# JTAG.net
KiCad netlist of a schematic drawn in Altium Designer
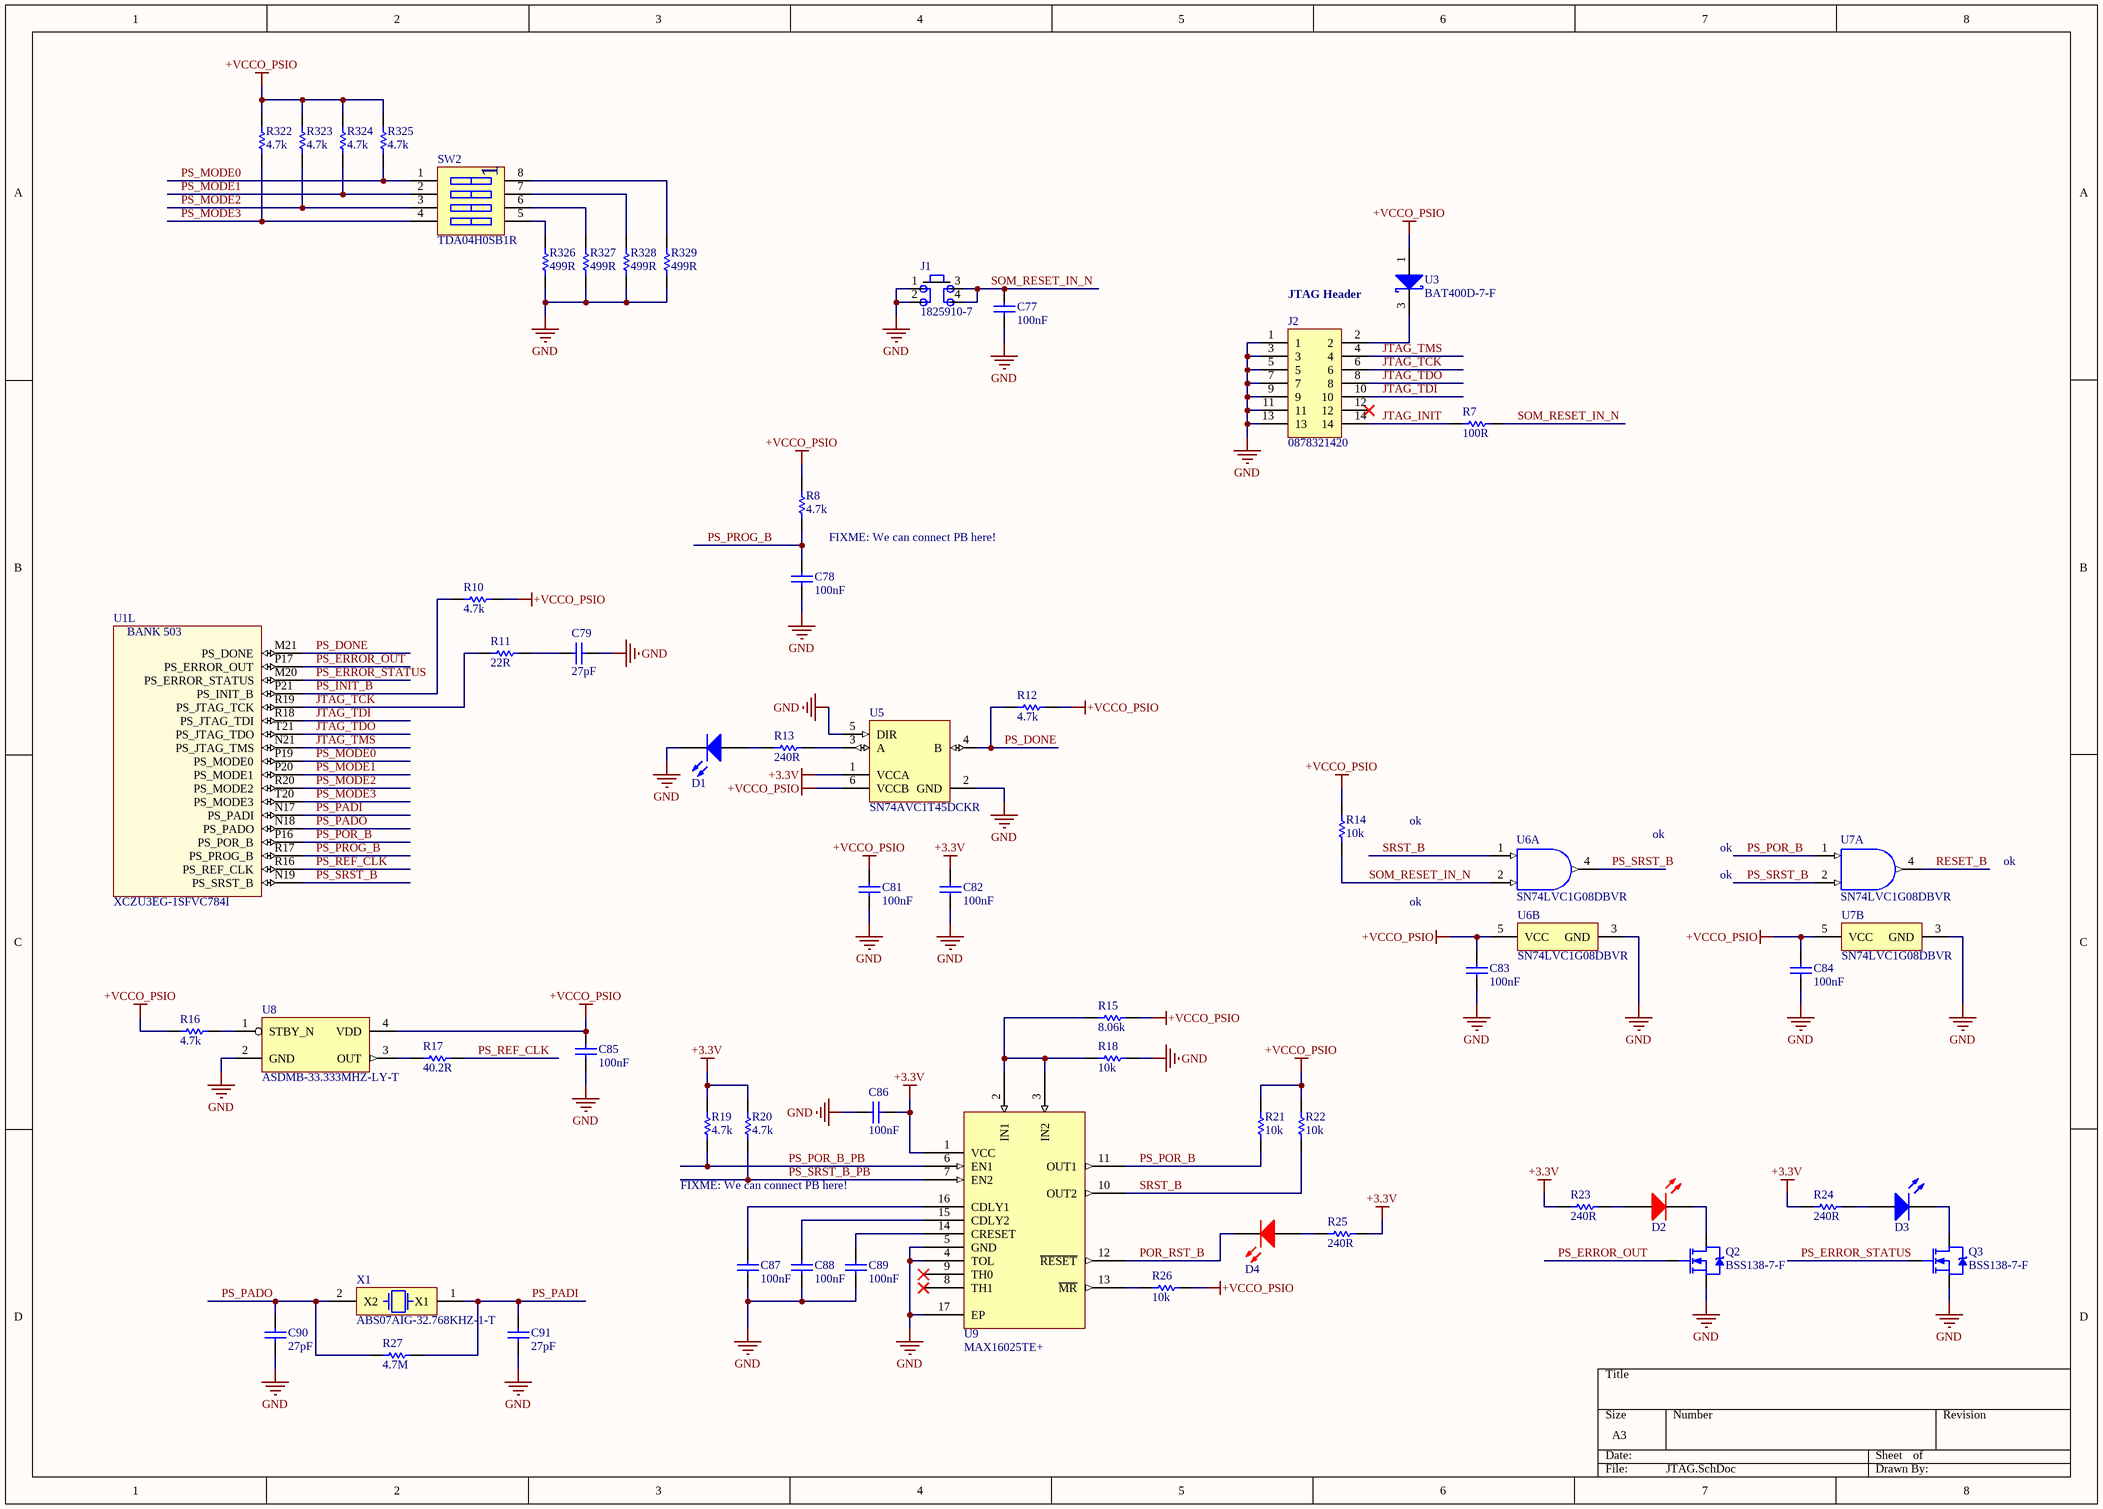
[diagram p0: JTAG.SchDoc]

(export (version "E")
  (design (tool "Eeschema 10.0.6"))
  (components
    (comp (ref "C77")
      (value "100nF")
      (footprint "CAPC1005L_0402")
      (description "CAP CER 0.1UF 25V X7R 0402")
      (fields (field (name "VOLTAGE") "25V") (field (name "TOLERANCE") "10%"))
      (libsource (lib "Ultrascale_SchLib") (part "CAPCER0402X7R100N25V_10T"))
    )
    (comp (ref "C78")
      (value "100nF")
      (footprint "CAPC1005L_0402")
      (description "CAP CER 0.1UF 25V X7R 0402")
      (fields (field (name "VOLTAGE") "25V") (field (name "TOLERANCE") "10%"))
      (libsource (lib "Ultrascale_SchLib") (part "CAPCER0402X7R100N25V_10T"))
    )
    (comp (ref "C79")
      (value "27pF")
      (footprint "CAPC1005L_0402")
      (description "CAP CER 27PF 50V C0G/NP0 0402")
      (fields (field (name "VOLTAGE") "50V") (field (name "TOLERANCE") "5%"))
      (libsource (lib "Ultrascale_SchLib") (part "CAPCER0402C0G27P50V_5T"))
    )
    (comp (ref "C81")
      (value "100nF")
      (footprint "CAPC1005L_0402")
      (description "CAP CER 0.1UF 25V X7R 0402")
      (fields (field (name "VOLTAGE") "25V") (field (name "TOLERANCE") "10%"))
      (libsource (lib "Ultrascale_SchLib") (part "CAPCER0402X7R100N25V_10T"))
    )
    (comp (ref "C82")
      (value "100nF")
      (footprint "CAPC1005L_0402")
      (description "CAP CER 0.1UF 25V X7R 0402")
      (fields (field (name "VOLTAGE") "25V") (field (name "TOLERANCE") "10%"))
      (libsource (lib "Ultrascale_SchLib") (part "CAPCER0402X7R100N25V_10T"))
    )
    (comp (ref "C83")
      (value "100nF")
      (footprint "CAPC1005L_0402")
      (description "CAP CER 0.1UF 25V X7R 0402")
      (fields (field (name "VOLTAGE") "25V") (field (name "TOLERANCE") "10%"))
      (libsource (lib "Ultrascale_SchLib") (part "CAPCER0402X7R100N25V_10T"))
    )
    (comp (ref "C84")
      (value "100nF")
      (footprint "CAPC1005L_0402")
      (description "CAP CER 0.1UF 25V X7R 0402")
      (fields (field (name "VOLTAGE") "25V") (field (name "TOLERANCE") "10%"))
      (libsource (lib "Ultrascale_SchLib") (part "CAPCER0402X7R100N25V_10T"))
    )
    (comp (ref "C85")
      (value "100nF")
      (footprint "CAPC1005L_0402")
      (description "CAP CER 0.1UF 25V X7R 0402")
      (fields (field (name "VOLTAGE") "25V") (field (name "TOLERANCE") "10%"))
      (libsource (lib "Ultrascale_SchLib") (part "CAPCER0402X7R100N25V_10T"))
    )
    (comp (ref "C86")
      (value "100nF")
      (footprint "CAPC1005L_0402")
      (description "CAP CER 0.1UF 25V X7R 0402")
      (fields (field (name "VOLTAGE") "25V") (field (name "TOLERANCE") "10%"))
      (libsource (lib "Ultrascale_SchLib") (part "CAPCER0402X7R100N25V_10T"))
    )
    (comp (ref "C87")
      (value "100nF")
      (footprint "CAPC1005L_0402")
      (description "CAP CER 0.1UF 25V X7R 0402")
      (fields (field (name "VOLTAGE") "25V") (field (name "TOLERANCE") "10%"))
      (libsource (lib "Ultrascale_SchLib") (part "CAPCER0402X7R100N25V_10T"))
    )
    (comp (ref "C88")
      (value "100nF")
      (footprint "CAPC1005L_0402")
      (description "CAP CER 0.1UF 25V X7R 0402")
      (fields (field (name "VOLTAGE") "25V") (field (name "TOLERANCE") "10%"))
      (libsource (lib "Ultrascale_SchLib") (part "CAPCER0402X7R100N25V_10T"))
    )
    (comp (ref "C89")
      (value "100nF")
      (footprint "CAPC1005L_0402")
      (description "CAP CER 0.1UF 25V X7R 0402")
      (fields (field (name "VOLTAGE") "25V") (field (name "TOLERANCE") "10%"))
      (libsource (lib "Ultrascale_SchLib") (part "CAPCER0402X7R100N25V_10T"))
    )
    (comp (ref "C90")
      (value "27pF")
      (footprint "CAPC1005L_0402")
      (description "CAP CER 27PF 50V C0G/NP0 0402")
      (fields (field (name "VOLTAGE") "50V") (field (name "TOLERANCE") "5%"))
      (libsource (lib "Ultrascale_SchLib") (part "CAPCER0402C0G27P50V_5T"))
    )
    (comp (ref "C91")
      (value "27pF")
      (footprint "CAPC1005L_0402")
      (description "CAP CER 27PF 50V C0G/NP0 0402")
      (fields (field (name "VOLTAGE") "50V") (field (name "TOLERANCE") "5%"))
      (libsource (lib "Ultrascale_SchLib") (part "CAPCER0402C0G27P50V_5T"))
    )
    (comp (ref "D1")
      (value "LED0603BLUE")
      (footprint "LED0603BLUE")
      (description "LED BLUE DIFFUSED 0603 SMD")
      (libsource (lib "Ultrascale_SchLib") (part "LED0603BLUE"))
    )
    (comp (ref "D2")
      (value "LED0603RED")
      (footprint "LED0603RED")
      (description "LED RED DIFFUSED 0603 SMD")
      (libsource (lib "Ultrascale_SchLib") (part "LED0603RED"))
    )
    (comp (ref "D3")
      (value "LED0603GREEN")
      (footprint "LED0603GREEN")
      (description "LED GREEN DIFFUSED 0603 SMD")
      (libsource (lib "Ultrascale_SchLib") (part "LED0603GREEN"))
    )
    (comp (ref "D4")
      (value "LED0603RED")
      (footprint "LED0603RED")
      (description "LED RED DIFFUSED 0603 SMD")
      (libsource (lib "Ultrascale_SchLib") (part "LED0603RED"))
    )
    (comp (ref "J1")
      (value "1825910-7")
      (footprint "PB_1825910-7")
      (description "SWITCH TACTILE SPST-NO 0.05A 24V")
      (libsource (lib "Ultrascale_SchLib") (part "1825910-7"))
    )
    (comp (ref "J2")
      (value "0878321420")
      (footprint "0878321420")
      (description "CONN HEADER 14POS 2MM VERT SMD")
      (libsource (lib "Ultrascale_SchLib") (part "0878321420"))
    )
    (comp (ref "Q2")
      (value "BSS138-7-F")
      (footprint "DIODES_SOT23")
      (description "MOSFET N-CH 50V 200MA SOT23-3")
      (libsource (lib "Ultrascale_SchLib") (part "BSS138-7-F"))
    )
    (comp (ref "Q3")
      (value "BSS138-7-F")
      (footprint "DIODES_SOT23")
      (description "MOSFET N-CH 50V 200MA SOT23-3")
      (libsource (lib "Ultrascale_SchLib") (part "BSS138-7-F"))
    )
    (comp (ref "R7")
      (value "100R")
      (footprint "RESC1005L_0402")
      (description "RES SMD 100 OHM 1% 1/10W 0402")
      (fields (field (name "POWER") "1/10W") (field (name "TOLERANCE") "1%"))
      (libsource (lib "Ultrascale_SchLib") (part "RES0402_100R_0W1_1T"))
    )
    (comp (ref "R8")
      (value "4.7k")
      (footprint "RESC1005L_0402")
      (description "RES SMD 4.7K OHM 1% 1/10W 0402")
      (fields (field (name "POWER") "1/10W") (field (name "TOLERANCE") "1%"))
      (libsource (lib "Ultrascale_SchLib") (part "RES0402_4K7_0W1_1T"))
    )
    (comp (ref "R10")
      (value "4.7k")
      (footprint "RESC1005L_0402")
      (description "RES SMD 4.7K OHM 1% 1/10W 0402")
      (fields (field (name "POWER") "1/10W") (field (name "TOLERANCE") "1%"))
      (libsource (lib "Ultrascale_SchLib") (part "RES0402_4K7_0W1_1T"))
    )
    (comp (ref "R11")
      (value "22R")
      (footprint "RESC1005L_0402")
      (description "RES SMD 22 OHM 1% 1/10W 0402")
      (fields (field (name "POWER") "1/10W") (field (name "TOLERANCE") "1%"))
      (libsource (lib "Ultrascale_SchLib") (part "RES0402_22R_0W1_1T"))
    )
    (comp (ref "R12")
      (value "4.7k")
      (footprint "RESC1005L_0402")
      (description "RES SMD 4.7K OHM 1% 1/10W 0402")
      (fields (field (name "POWER") "1/10W") (field (name "TOLERANCE") "1%"))
      (libsource (lib "Ultrascale_SchLib") (part "RES0402_4K7_0W1_1T"))
    )
    (comp (ref "R13")
      (value "240R")
      (footprint "RESC1005L_0402")
      (description "RES SMD 240 OHM 1% 1/10W 0402")
      (fields (field (name "POWER") "1/10W") (field (name "TOLERANCE") "1%"))
      (libsource (lib "Ultrascale_SchLib") (part "RES0402_240R_0W1_1T"))
    )
    (comp (ref "R14")
      (value "10k")
      (footprint "RESC1005L_0402")
      (description "RES SMD 10K OHM 0.5% 1/16W 0402")
      (fields (field (name "POWER") "1/16W") (field (name "TOLERANCE") "0.5%"))
      (libsource (lib "Ultrascale_SchLib") (part "RES0402_10K_0W1_05T"))
    )
    (comp (ref "R15")
      (value "8.06k")
      (footprint "RESC1005L_0402")
      (description "RES SMD 8.06K OHM 1% 1/10W 0402")
      (fields (field (name "POWER") "1/10W") (field (name "TOLERANCE") "1%"))
      (libsource (lib "Ultrascale_SchLib") (part "RES0402_8K06_0W1_1T"))
    )
    (comp (ref "R16")
      (value "4.7k")
      (footprint "RESC1005L_0402")
      (description "RES SMD 4.7K OHM 1% 1/10W 0402")
      (fields (field (name "POWER") "1/10W") (field (name "TOLERANCE") "1%"))
      (libsource (lib "Ultrascale_SchLib") (part "RES0402_4K7_0W1_1T"))
    )
    (comp (ref "R17")
      (value "40.2R")
      (footprint "RESC1005L_0402")
      (description "RES SMD 40.2 OHM 1% 1/10W 0402")
      (fields (field (name "POWER") "1/10W") (field (name "TOLERANCE") "1%"))
      (libsource (lib "Ultrascale_SchLib") (part "RES0402_40R2_0W1_1T"))
    )
    (comp (ref "R18")
      (value "10k")
      (footprint "RESC1005L_0402")
      (description "RES SMD 10K OHM 0.5% 1/16W 0402")
      (fields (field (name "POWER") "1/16W") (field (name "TOLERANCE") "0.5%"))
      (libsource (lib "Ultrascale_SchLib") (part "RES0402_10K_0W1_05T"))
    )
    (comp (ref "R19")
      (value "4.7k")
      (footprint "RESC1005L_0402")
      (description "RES SMD 4.7K OHM 1% 1/10W 0402")
      (fields (field (name "POWER") "1/10W") (field (name "TOLERANCE") "1%"))
      (libsource (lib "Ultrascale_SchLib") (part "RES0402_4K7_0W1_1T"))
    )
    (comp (ref "R20")
      (value "4.7k")
      (footprint "RESC1005L_0402")
      (description "RES SMD 4.7K OHM 1% 1/10W 0402")
      (fields (field (name "POWER") "1/10W") (field (name "TOLERANCE") "1%"))
      (libsource (lib "Ultrascale_SchLib") (part "RES0402_4K7_0W1_1T"))
    )
    (comp (ref "R21")
      (value "10k")
      (footprint "RESC1005L_0402")
      (description "RES SMD 10K OHM 0.5% 1/16W 0402")
      (fields (field (name "POWER") "1/16W") (field (name "TOLERANCE") "0.5%"))
      (libsource (lib "Ultrascale_SchLib") (part "RES0402_10K_0W1_05T"))
    )
    (comp (ref "R22")
      (value "10k")
      (footprint "RESC1005L_0402")
      (description "RES SMD 10K OHM 0.5% 1/16W 0402")
      (fields (field (name "POWER") "1/16W") (field (name "TOLERANCE") "0.5%"))
      (libsource (lib "Ultrascale_SchLib") (part "RES0402_10K_0W1_05T"))
    )
    (comp (ref "R23")
      (value "240R")
      (footprint "RESC1005L_0402")
      (description "RES SMD 240 OHM 1% 1/10W 0402")
      (fields (field (name "POWER") "1/10W") (field (name "TOLERANCE") "1%"))
      (libsource (lib "Ultrascale_SchLib") (part "RES0402_240R_0W1_1T"))
    )
    (comp (ref "R24")
      (value "240R")
      (footprint "RESC1005L_0402")
      (description "RES SMD 240 OHM 1% 1/10W 0402")
      (fields (field (name "POWER") "1/10W") (field (name "TOLERANCE") "1%"))
      (libsource (lib "Ultrascale_SchLib") (part "RES0402_240R_0W1_1T"))
    )
    (comp (ref "R25")
      (value "240R")
      (footprint "RESC1005L_0402")
      (description "RES SMD 240 OHM 1% 1/10W 0402")
      (fields (field (name "POWER") "1/10W") (field (name "TOLERANCE") "1%"))
      (libsource (lib "Ultrascale_SchLib") (part "RES0402_240R_0W1_1T"))
    )
    (comp (ref "R26")
      (value "10k")
      (footprint "RESC1005L_0402")
      (description "RES SMD 10K OHM 0.5% 1/16W 0402")
      (fields (field (name "POWER") "1/16W") (field (name "TOLERANCE") "0.5%"))
      (libsource (lib "Ultrascale_SchLib") (part "RES0402_10K_0W1_05T"))
    )
    (comp (ref "R27")
      (value "4.7M")
      (footprint "RESC1005L_0402")
      (description "RES SMD 4.7M OHM 5% 1/16W 0402")
      (fields (field (name "POWER") "1/10W") (field (name "TOLERANCE") "5%"))
      (libsource (lib "Ultrascale_SchLib") (part "RES0402_4M7_0W1_5T"))
    )
    (comp (ref "R322")
      (value "4.7k")
      (footprint "RESC1005L_0402")
      (description "RES SMD 4.7K OHM 1% 1/10W 0402")
      (fields (field (name "POWER") "1/10W") (field (name "TOLERANCE") "1%"))
      (libsource (lib "Ultrascale_SchLib") (part "RES0402_4K7_0W1_1T"))
    )
    (comp (ref "R323")
      (value "4.7k")
      (footprint "RESC1005L_0402")
      (description "RES SMD 4.7K OHM 1% 1/10W 0402")
      (fields (field (name "POWER") "1/10W") (field (name "TOLERANCE") "1%"))
      (libsource (lib "Ultrascale_SchLib") (part "RES0402_4K7_0W1_1T"))
    )
    (comp (ref "R324")
      (value "4.7k")
      (footprint "RESC1005L_0402")
      (description "RES SMD 4.7K OHM 1% 1/10W 0402")
      (fields (field (name "POWER") "1/10W") (field (name "TOLERANCE") "1%"))
      (libsource (lib "Ultrascale_SchLib") (part "RES0402_4K7_0W1_1T"))
    )
    (comp (ref "R325")
      (value "4.7k")
      (footprint "RESC1005L_0402")
      (description "RES SMD 4.7K OHM 1% 1/10W 0402")
      (fields (field (name "POWER") "1/10W") (field (name "TOLERANCE") "1%"))
      (libsource (lib "Ultrascale_SchLib") (part "RES0402_4K7_0W1_1T"))
    )
    (comp (ref "R326")
      (value "499R")
      (footprint "RESC1005L_0402")
      (description "RES SMD 499 OHM 1% 1/16W 0402")
      (fields (field (name "POWER") "1/10W") (field (name "TOLERANCE") "1%"))
      (libsource (lib "Ultrascale_SchLib") (part "RES0402_499R_0W1_1T"))
    )
    (comp (ref "R327")
      (value "499R")
      (footprint "RESC1005L_0402")
      (description "RES SMD 499 OHM 1% 1/16W 0402")
      (fields (field (name "POWER") "1/10W") (field (name "TOLERANCE") "1%"))
      (libsource (lib "Ultrascale_SchLib") (part "RES0402_499R_0W1_1T"))
    )
    (comp (ref "R328")
      (value "499R")
      (footprint "RESC1005L_0402")
      (description "RES SMD 499 OHM 1% 1/16W 0402")
      (fields (field (name "POWER") "1/10W") (field (name "TOLERANCE") "1%"))
      (libsource (lib "Ultrascale_SchLib") (part "RES0402_499R_0W1_1T"))
    )
    (comp (ref "R329")
      (value "499R")
      (footprint "RESC1005L_0402")
      (description "RES SMD 499 OHM 1% 1/16W 0402")
      (fields (field (name "POWER") "1/10W") (field (name "TOLERANCE") "1%"))
      (libsource (lib "Ultrascale_SchLib") (part "RES0402_499R_0W1_1T"))
    )
    (comp (ref "SW2")
      (value "TDA04H0SB1R")
      (footprint "4POS_DIP_SWITCH")
      (description "SWITCH SLIDE DIP SPST 25MA 24V")
      (libsource (lib "Ultrascale_SchLib") (part "TDA04H0SB1R"))
    )
    (comp (ref "U1")
      (value "XCZU3EG-1SFVC784I")
      (footprint "BGA784x28")
      (description "IC FPGA 252 I/O 784FCBGA - XILINX ZYNQ ULTRASCALE+")
      (libsource (lib "Ultrascale_SchLib") (part "XCZU3EG-1SFVC784I"))
    )
    (comp (ref "U3")
      (value "BAT400D-7-F")
      (footprint "BAT400D-7-F _SOT23")
      (description "DIODE SCHOTTKY 40V 500MA SOT23-3")
      (libsource (lib "Ultrascale_SchLib") (part "BAT400D-7-F"))
    )
    (comp (ref "U5")
      (value "SN74AVC1T45DCKR")
      (footprint "DCK0006A_N")
      (fields (field (name "GENERIC PART NUMBER") "SN74AVC1T45"))
      (libsource (lib "Ultrascale_SchLib") (part "SN74AVC1T45DCKR"))
    )
    (comp (ref "U6")
      (value "SN74LVC1G08DBVR")
      (footprint "DBV0005A_N")
      (description "Single 2-Input Positive-AND Gate, DBV0005A, LARGE T&R")
      (fields (field (name "GENERIC PART NUMBER") "SN74LVC1G08"))
      (libsource (lib "Ultrascale_SchLib") (part "SN74LVC1G08DBVR"))
    )
    (comp (ref "U7")
      (value "SN74LVC1G08DBVR")
      (footprint "DBV0005A_N")
      (description "Single 2-Input Positive-AND Gate, DBV0005A, LARGE T&R")
      (fields (field (name "GENERIC PART NUMBER") "SN74LVC1G08"))
      (libsource (lib "Ultrascale_SchLib") (part "SN74LVC1G08DBVR"))
    )
    (comp (ref "U8")
      (value "ASDMB-33.333MHZ-LY-T")
      (footprint "ASDMB")
      (description "OSC MEMS 33.333MHZ CMOS SMD")
      (libsource (lib "Ultrascale_SchLib") (part "ASDMB-33.333MHZ-LY-T"))
    )
    (comp (ref "U9")
      (value "MAX16025TE+")
      (footprint "T1644+4_L")
      (description "IC SUPERVISORY CIRC DL 16TQFN")
      (libsource (lib "Ultrascale_SchLib") (part "MAX16025TE+"))
    )
    (comp (ref "X1")
      (value "ABS07AIG-32.768KHZ-1-T")
      (footprint "ABS07")
      (description "CRYSTAL 32.768KHZ 12.5PF SMD")
      (libsource (lib "Ultrascale_SchLib") (part "ABS07AIG-32.768KHZ-1-T"))
    )
  )
  (nets
    (net (code "1") (name "+3.3V") (class "Default")
      (node (ref "C82") (pin "1") (pinfunction "1_1") (pintype "passive"))
      (node (ref "C86") (pin "1") (pinfunction "1_1") (pintype "passive"))
      (node (ref "R19") (pin "1") (pinfunction "1_1") (pintype "passive"))
      (node (ref "R20") (pin "1") (pinfunction "1_1") (pintype "passive"))
      (node (ref "R23") (pin "1") (pinfunction "1_1") (pintype "passive"))
      (node (ref "R24") (pin "1") (pinfunction "1_1") (pintype "passive"))
      (node (ref "R25") (pin "2") (pinfunction "2_2") (pintype "passive"))
      (node (ref "U5") (pin "1") (pinfunction "VCCA_1") (pintype "power_in"))
      (node (ref "U9") (pin "1") (pinfunction "VCC_1") (pintype "passive"))
    )
    (net (code "2") (name "+VCCO_PSIO") (class "Default")
      (node (ref "C81") (pin "1") (pinfunction "1_1") (pintype "passive"))
      (node (ref "C83") (pin "1") (pinfunction "1_1") (pintype "passive"))
      (node (ref "C84") (pin "1") (pinfunction "1_1") (pintype "passive"))
      (node (ref "C85") (pin "1") (pinfunction "1_1") (pintype "passive"))
      (node (ref "R10") (pin "2") (pinfunction "2_2") (pintype "passive"))
      (node (ref "R12") (pin "2") (pinfunction "2_2") (pintype "passive"))
      (node (ref "R14") (pin "1") (pinfunction "1_1") (pintype "passive"))
      (node (ref "R15") (pin "2") (pinfunction "2_2") (pintype "passive"))
      (node (ref "R16") (pin "1") (pinfunction "1_1") (pintype "passive"))
      (node (ref "R21") (pin "1") (pinfunction "1_1") (pintype "passive"))
      (node (ref "R22") (pin "1") (pinfunction "1_1") (pintype "passive"))
      (node (ref "R26") (pin "1") (pinfunction "1_1") (pintype "passive"))
      (node (ref "R322") (pin "2") (pinfunction "2_2") (pintype "passive"))
      (node (ref "R323") (pin "2") (pinfunction "2_2") (pintype "passive"))
      (node (ref "R324") (pin "2") (pinfunction "2_2") (pintype "passive"))
      (node (ref "R325") (pin "2") (pinfunction "2_2") (pintype "passive"))
      (node (ref "R8") (pin "1") (pinfunction "1_1") (pintype "passive"))
      (node (ref "U3") (pin "1") (pinfunction "A_1") (pintype "passive"))
      (node (ref "U5") (pin "6") (pinfunction "VCCB_6") (pintype "power_in"))
      (node (ref "U6") (pin "5") (pinfunction "VCC_5") (pintype "power_in"))
      (node (ref "U7") (pin "5") (pinfunction "VCC_5") (pintype "power_in"))
      (node (ref "U8") (pin "4") (pinfunction "VDD_4") (pintype "passive"))
    )
    (net (code "3") (name "/JTAG_INIT") (class "Default")
      (node (ref "J2") (pin "14") (pinfunction "14_14") (pintype "power_in"))
      (node (ref "R7") (pin "1") (pinfunction "1_1") (pintype "passive"))
    )
    (net (code "4") (name "/JTAG_TCK") (class "Default")
      (node (ref "J2") (pin "6") (pinfunction "6_6") (pintype "power_in"))
      (node (ref "R11") (pin "1") (pinfunction "1_1") (pintype "passive"))
      (node (ref "U1") (pin "R19") (pinfunction "PS_JTAG_TCK_R19") (pintype "bidirectional"))
    )
    (net (code "5") (name "/JTAG_TDI") (class "Default")
      (node (ref "J2") (pin "10") (pinfunction "10_10") (pintype "power_in"))
      (node (ref "U1") (pin "R18") (pinfunction "PS_JTAG_TDI_R18") (pintype "bidirectional"))
    )
    (net (code "6") (name "/JTAG_TDO") (class "Default")
      (node (ref "J2") (pin "8") (pinfunction "8_8") (pintype "power_in"))
      (node (ref "U1") (pin "T21") (pinfunction "PS_JTAG_TDO_T21") (pintype "bidirectional"))
    )
    (net (code "7") (name "/JTAG_TMS") (class "Default")
      (node (ref "J2") (pin "4") (pinfunction "4_4") (pintype "power_in"))
      (node (ref "U1") (pin "N21") (pinfunction "PS_JTAG_TMS_N21") (pintype "bidirectional"))
    )
    (net (code "8") (name "/POR_RST_B") (class "Default")
      (node (ref "D4") (pin "2") (pinfunction "K_2") (pintype "passive"))
      (node (ref "U9") (pin "12") (pinfunction "~{RESET}_12") (pintype "output"))
    )
    (net (code "9") (name "/PS_DONE") (class "Default")
      (node (ref "R12") (pin "1") (pinfunction "1_1") (pintype "passive"))
      (node (ref "U1") (pin "M21") (pinfunction "PS_DONE_M21") (pintype "bidirectional"))
      (node (ref "U5") (pin "4") (pinfunction "B_4") (pintype "bidirectional"))
    )
    (net (code "10") (name "/PS_ERROR_OUT") (class "Default")
      (node (ref "Q2") (pin "G") (pinfunction "G_G") (pintype "passive"))
      (node (ref "U1") (pin "P17") (pinfunction "PS_ERROR_OUT_P17") (pintype "bidirectional"))
    )
    (net (code "11") (name "/PS_ERROR_STATUS") (class "Default")
      (node (ref "Q3") (pin "G") (pinfunction "G_G") (pintype "passive"))
      (node (ref "U1") (pin "M20") (pinfunction "PS_ERROR_STATUS_M20") (pintype "bidirectional"))
    )
    (net (code "12") (name "/PS_INIT_B") (class "Default")
      (node (ref "R10") (pin "1") (pinfunction "1_1") (pintype "passive"))
      (node (ref "U1") (pin "P21") (pinfunction "PS_INIT_B_P21") (pintype "bidirectional"))
    )
    (net (code "13") (name "/PS_MODE0") (class "Default")
      (node (ref "R325") (pin "1") (pinfunction "1_1") (pintype "passive"))
      (node (ref "SW2") (pin "1") (pinfunction "1_1") (pintype "power_in"))
      (node (ref "U1") (pin "P19") (pinfunction "PS_MODE0_P19") (pintype "bidirectional"))
    )
    (net (code "14") (name "/PS_MODE1") (class "Default")
      (node (ref "R324") (pin "1") (pinfunction "1_1") (pintype "passive"))
      (node (ref "SW2") (pin "2") (pinfunction "2_2") (pintype "power_in"))
      (node (ref "U1") (pin "P20") (pinfunction "PS_MODE1_P20") (pintype "bidirectional"))
    )
    (net (code "15") (name "/PS_MODE2") (class "Default")
      (node (ref "R323") (pin "1") (pinfunction "1_1") (pintype "passive"))
      (node (ref "SW2") (pin "3") (pinfunction "3_3") (pintype "power_in"))
      (node (ref "U1") (pin "R20") (pinfunction "PS_MODE2_R20") (pintype "bidirectional"))
    )
    (net (code "16") (name "/PS_MODE3") (class "Default")
      (node (ref "R322") (pin "1") (pinfunction "1_1") (pintype "passive"))
      (node (ref "SW2") (pin "4") (pinfunction "4_4") (pintype "power_in"))
      (node (ref "U1") (pin "T20") (pinfunction "PS_MODE3_T20") (pintype "bidirectional"))
    )
    (net (code "17") (name "/PS_PADI") (class "Default")
      (node (ref "C91") (pin "1") (pinfunction "1_1") (pintype "passive"))
      (node (ref "R27") (pin "2") (pinfunction "2_2") (pintype "passive"))
      (node (ref "U1") (pin "N17") (pinfunction "PS_PADI_N17") (pintype "bidirectional"))
      (node (ref "X1") (pin "1") (pinfunction "X1_1") (pintype "passive"))
    )
    (net (code "18") (name "/PS_PADO") (class "Default")
      (node (ref "C90") (pin "1") (pinfunction "1_1") (pintype "passive"))
      (node (ref "R27") (pin "1") (pinfunction "1_1") (pintype "passive"))
      (node (ref "U1") (pin "N18") (pinfunction "PS_PADO_N18") (pintype "bidirectional"))
      (node (ref "X1") (pin "2") (pinfunction "X2_2") (pintype "passive"))
    )
    (net (code "19") (name "/PS_POR_B") (class "Default")
      (node (ref "R21") (pin "2") (pinfunction "2_2") (pintype "passive"))
      (node (ref "U1") (pin "P16") (pinfunction "PS_POR_B_P16") (pintype "bidirectional"))
      (node (ref "U7") (pin "1") (pinfunction "A_1") (pintype "input"))
      (node (ref "U9") (pin "11") (pinfunction "OUT1_11") (pintype "output"))
    )
    (net (code "20") (name "/PS_POR_B_PB") (class "Default")
      (node (ref "R19") (pin "2") (pinfunction "2_2") (pintype "passive"))
      (node (ref "U9") (pin "6") (pinfunction "EN1_6") (pintype "input"))
    )
    (net (code "21") (name "/PS_PROG_B") (class "Default")
      (node (ref "C78") (pin "1") (pinfunction "1_1") (pintype "passive"))
      (node (ref "R8") (pin "2") (pinfunction "2_2") (pintype "passive"))
      (node (ref "U1") (pin "R17") (pinfunction "PS_PROG_B_R17") (pintype "bidirectional"))
    )
    (net (code "22") (name "/PS_REF_CLK") (class "Default")
      (node (ref "R17") (pin "2") (pinfunction "2_2") (pintype "passive"))
      (node (ref "U1") (pin "R16") (pinfunction "PS_REF_CLK_R16") (pintype "bidirectional"))
    )
    (net (code "23") (name "/PS_SRST_B") (class "Default")
      (node (ref "U1") (pin "N19") (pinfunction "PS_SRST_B_N19") (pintype "bidirectional"))
      (node (ref "U6") (pin "4") (pinfunction "Y_4") (pintype "output"))
      (node (ref "U7") (pin "2") (pinfunction "B_2") (pintype "input"))
    )
    (net (code "24") (name "/PS_SRST_B_PB") (class "Default")
      (node (ref "R20") (pin "2") (pinfunction "2_2") (pintype "passive"))
      (node (ref "U9") (pin "7") (pinfunction "EN2_7") (pintype "input"))
    )
    (net (code "25") (name "/RESET_B") (class "Default")
      (node (ref "U7") (pin "4") (pinfunction "Y_4") (pintype "output"))
    )
    (net (code "26") (name "/SOM_RESET_IN_N") (class "Default")
      (node (ref "C77") (pin "2") (pinfunction "2_2") (pintype "passive"))
      (node (ref "J1") (pin "3") (pinfunction "3_3") (pintype "passive"))
      (node (ref "J1") (pin "4") (pinfunction "4_4") (pintype "passive"))
      (node (ref "R14") (pin "2") (pinfunction "2_2") (pintype "passive"))
      (node (ref "R7") (pin "2") (pinfunction "2_2") (pintype "passive"))
      (node (ref "U6") (pin "2") (pinfunction "B_2") (pintype "input"))
    )
    (net (code "27") (name "/SRST_B") (class "Default")
      (node (ref "R22") (pin "2") (pinfunction "2_2") (pintype "passive"))
      (node (ref "U6") (pin "1") (pinfunction "A_1") (pintype "input"))
      (node (ref "U9") (pin "10") (pinfunction "OUT2_10") (pintype "output"))
    )
    (net (code "28") (name "GND") (class "Default")
      (node (ref "C77") (pin "1") (pinfunction "1_1") (pintype "passive"))
      (node (ref "C78") (pin "2") (pinfunction "2_2") (pintype "passive"))
      (node (ref "C79") (pin "2") (pinfunction "2_2") (pintype "passive"))
      (node (ref "C81") (pin "2") (pinfunction "2_2") (pintype "passive"))
      (node (ref "C82") (pin "2") (pinfunction "2_2") (pintype "passive"))
      (node (ref "C83") (pin "2") (pinfunction "2_2") (pintype "passive"))
      (node (ref "C84") (pin "2") (pinfunction "2_2") (pintype "passive"))
      (node (ref "C85") (pin "2") (pinfunction "2_2") (pintype "passive"))
      (node (ref "C86") (pin "2") (pinfunction "2_2") (pintype "passive"))
      (node (ref "C87") (pin "2") (pinfunction "2_2") (pintype "passive"))
      (node (ref "C88") (pin "2") (pinfunction "2_2") (pintype "passive"))
      (node (ref "C89") (pin "2") (pinfunction "2_2") (pintype "passive"))
      (node (ref "C90") (pin "2") (pinfunction "2_2") (pintype "passive"))
      (node (ref "C91") (pin "2") (pinfunction "2_2") (pintype "passive"))
      (node (ref "D1") (pin "2") (pinfunction "K_2") (pintype "passive"))
      (node (ref "J1") (pin "1") (pinfunction "1_1") (pintype "passive"))
      (node (ref "J1") (pin "2") (pinfunction "2_2") (pintype "passive"))
      (node (ref "J2") (pin "1") (pinfunction "1_1") (pintype "power_in"))
      (node (ref "J2") (pin "11") (pinfunction "11_11") (pintype "power_in"))
      (node (ref "J2") (pin "13") (pinfunction "13_13") (pintype "power_in"))
      (node (ref "J2") (pin "3") (pinfunction "3_3") (pintype "power_in"))
      (node (ref "J2") (pin "5") (pinfunction "5_5") (pintype "power_in"))
      (node (ref "J2") (pin "7") (pinfunction "7_7") (pintype "power_in"))
      (node (ref "J2") (pin "9") (pinfunction "9_9") (pintype "power_in"))
      (node (ref "Q2") (pin "S") (pinfunction "S_S") (pintype "passive"))
      (node (ref "Q3") (pin "S") (pinfunction "S_S") (pintype "passive"))
      (node (ref "R18") (pin "2") (pinfunction "2_2") (pintype "passive"))
      (node (ref "R326") (pin "2") (pinfunction "2_2") (pintype "passive"))
      (node (ref "R327") (pin "2") (pinfunction "2_2") (pintype "passive"))
      (node (ref "R328") (pin "2") (pinfunction "2_2") (pintype "passive"))
      (node (ref "R329") (pin "2") (pinfunction "2_2") (pintype "passive"))
      (node (ref "U5") (pin "2") (pinfunction "GND_2") (pintype "power_in"))
      (node (ref "U5") (pin "5") (pinfunction "DIR_5") (pintype "input"))
      (node (ref "U6") (pin "3") (pinfunction "GND_3") (pintype "power_in"))
      (node (ref "U7") (pin "3") (pinfunction "GND_3") (pintype "power_in"))
      (node (ref "U8") (pin "2") (pinfunction "GND_2") (pintype "passive"))
      (node (ref "U9") (pin "17") (pinfunction "EP_17") (pintype "passive"))
      (node (ref "U9") (pin "4") (pinfunction "TOL_4") (pintype "passive"))
      (node (ref "U9") (pin "5") (pinfunction "GND_5") (pintype "passive"))
    )
    (net (code "29") (name "Net-(C79-Pad1)") (class "Default")
      (node (ref "C79") (pin "1") (pinfunction "1_1") (pintype "passive"))
      (node (ref "R11") (pin "2") (pinfunction "2_2") (pintype "passive"))
    )
    (net (code "30") (name "Net-(D1-A)") (class "Default")
      (node (ref "D1") (pin "1") (pinfunction "A_1") (pintype "passive"))
      (node (ref "R13") (pin "1") (pinfunction "1_1") (pintype "passive"))
    )
    (net (code "31") (name "Net-(D2-A)") (class "Default")
      (node (ref "D2") (pin "1") (pinfunction "A_1") (pintype "passive"))
      (node (ref "R23") (pin "2") (pinfunction "2_2") (pintype "passive"))
    )
    (net (code "32") (name "Net-(D2-K)") (class "Default")
      (node (ref "D2") (pin "2") (pinfunction "K_2") (pintype "passive"))
      (node (ref "Q2") (pin "D") (pinfunction "D_D") (pintype "passive"))
    )
    (net (code "33") (name "Net-(D3-A)") (class "Default")
      (node (ref "D3") (pin "1") (pinfunction "A_1") (pintype "passive"))
      (node (ref "R24") (pin "2") (pinfunction "2_2") (pintype "passive"))
    )
    (net (code "34") (name "Net-(D3-K)") (class "Default")
      (node (ref "D3") (pin "2") (pinfunction "K_2") (pintype "passive"))
      (node (ref "Q3") (pin "D") (pinfunction "D_D") (pintype "passive"))
    )
    (net (code "35") (name "Net-(D4-A)") (class "Default")
      (node (ref "D4") (pin "1") (pinfunction "A_1") (pintype "passive"))
      (node (ref "R25") (pin "1") (pinfunction "1_1") (pintype "passive"))
    )
    (net (code "36") (name "Net-(R326-Pad1)") (class "Default")
      (node (ref "R326") (pin "1") (pinfunction "1_1") (pintype "passive"))
      (node (ref "SW2") (pin "5") (pinfunction "5_5") (pintype "power_in"))
    )
    (net (code "37") (name "Net-(R327-Pad1)") (class "Default")
      (node (ref "R327") (pin "1") (pinfunction "1_1") (pintype "passive"))
      (node (ref "SW2") (pin "6") (pinfunction "6_6") (pintype "power_in"))
    )
    (net (code "38") (name "Net-(R328-Pad1)") (class "Default")
      (node (ref "R328") (pin "1") (pinfunction "1_1") (pintype "passive"))
      (node (ref "SW2") (pin "7") (pinfunction "7_7") (pintype "power_in"))
    )
    (net (code "39") (name "Net-(R329-Pad1)") (class "Default")
      (node (ref "R329") (pin "1") (pinfunction "1_1") (pintype "passive"))
      (node (ref "SW2") (pin "8") (pinfunction "8_8") (pintype "power_in"))
    )
    (net (code "40") (name "Net-(U3-K)") (class "Default")
      (node (ref "J2") (pin "2") (pinfunction "2_2") (pintype "power_in"))
      (node (ref "U3") (pin "3") (pinfunction "K_3") (pintype "passive"))
    )
    (net (code "41") (name "Net-(U5-A)") (class "Default")
      (node (ref "R13") (pin "2") (pinfunction "2_2") (pintype "passive"))
      (node (ref "U5") (pin "3") (pinfunction "A_3") (pintype "bidirectional"))
    )
    (net (code "42") (name "Net-(U8-OUT)") (class "Default")
      (node (ref "R17") (pin "1") (pinfunction "1_1") (pintype "passive"))
      (node (ref "U8") (pin "3") (pinfunction "OUT_3") (pintype "output"))
    )
    (net (code "43") (name "Net-(U8-STBY_N)") (class "Default")
      (node (ref "R16") (pin "2") (pinfunction "2_2") (pintype "passive"))
      (node (ref "U8") (pin "1") (pinfunction "STBY_N_1") (pintype "passive"))
    )
    (net (code "44") (name "Net-(U9-CDLY1)") (class "Default")
      (node (ref "C87") (pin "1") (pinfunction "1_1") (pintype "passive"))
      (node (ref "U9") (pin "16") (pinfunction "CDLY1_16") (pintype "passive"))
    )
    (net (code "45") (name "Net-(U9-CDLY2)") (class "Default")
      (node (ref "C88") (pin "1") (pinfunction "1_1") (pintype "passive"))
      (node (ref "U9") (pin "15") (pinfunction "CDLY2_15") (pintype "passive"))
    )
    (net (code "46") (name "Net-(U9-CRESET)") (class "Default")
      (node (ref "C89") (pin "1") (pinfunction "1_1") (pintype "passive"))
      (node (ref "U9") (pin "14") (pinfunction "CRESET_14") (pintype "passive"))
    )
    (net (code "47") (name "Net-(U9-IN1)") (class "Default")
      (node (ref "R15") (pin "1") (pinfunction "1_1") (pintype "passive"))
      (node (ref "R18") (pin "1") (pinfunction "1_1") (pintype "passive"))
      (node (ref "U9") (pin "2") (pinfunction "IN1_2") (pintype "input"))
      (node (ref "U9") (pin "3") (pinfunction "IN2_3") (pintype "input"))
    )
    (net (code "48") (name "Net-(U9-~{MR})") (class "Default")
      (node (ref "R26") (pin "2") (pinfunction "2_2") (pintype "passive"))
      (node (ref "U9") (pin "13") (pinfunction "~{MR}_13") (pintype "output"))
    )
    (net (code "49") (name "unconnected-(J2-Pad12)") (class "Default")
      (node (ref "J2") (pin "12") (pinfunction "12_12") (pintype "power_in+no_connect"))
    )
    (net (code "50") (name "unconnected-(U9-TH0-Pad9)") (class "Default")
      (node (ref "U9") (pin "9") (pinfunction "TH0_9") (pintype "passive+no_connect"))
    )
    (net (code "51") (name "unconnected-(U9-TH1-Pad8)") (class "Default")
      (node (ref "U9") (pin "8") (pinfunction "TH1_8") (pintype "passive+no_connect"))
    )
  )
)
